# HYDRA_V4_NAV.net
KiCad netlist of a schematic drawn in Altium Designer
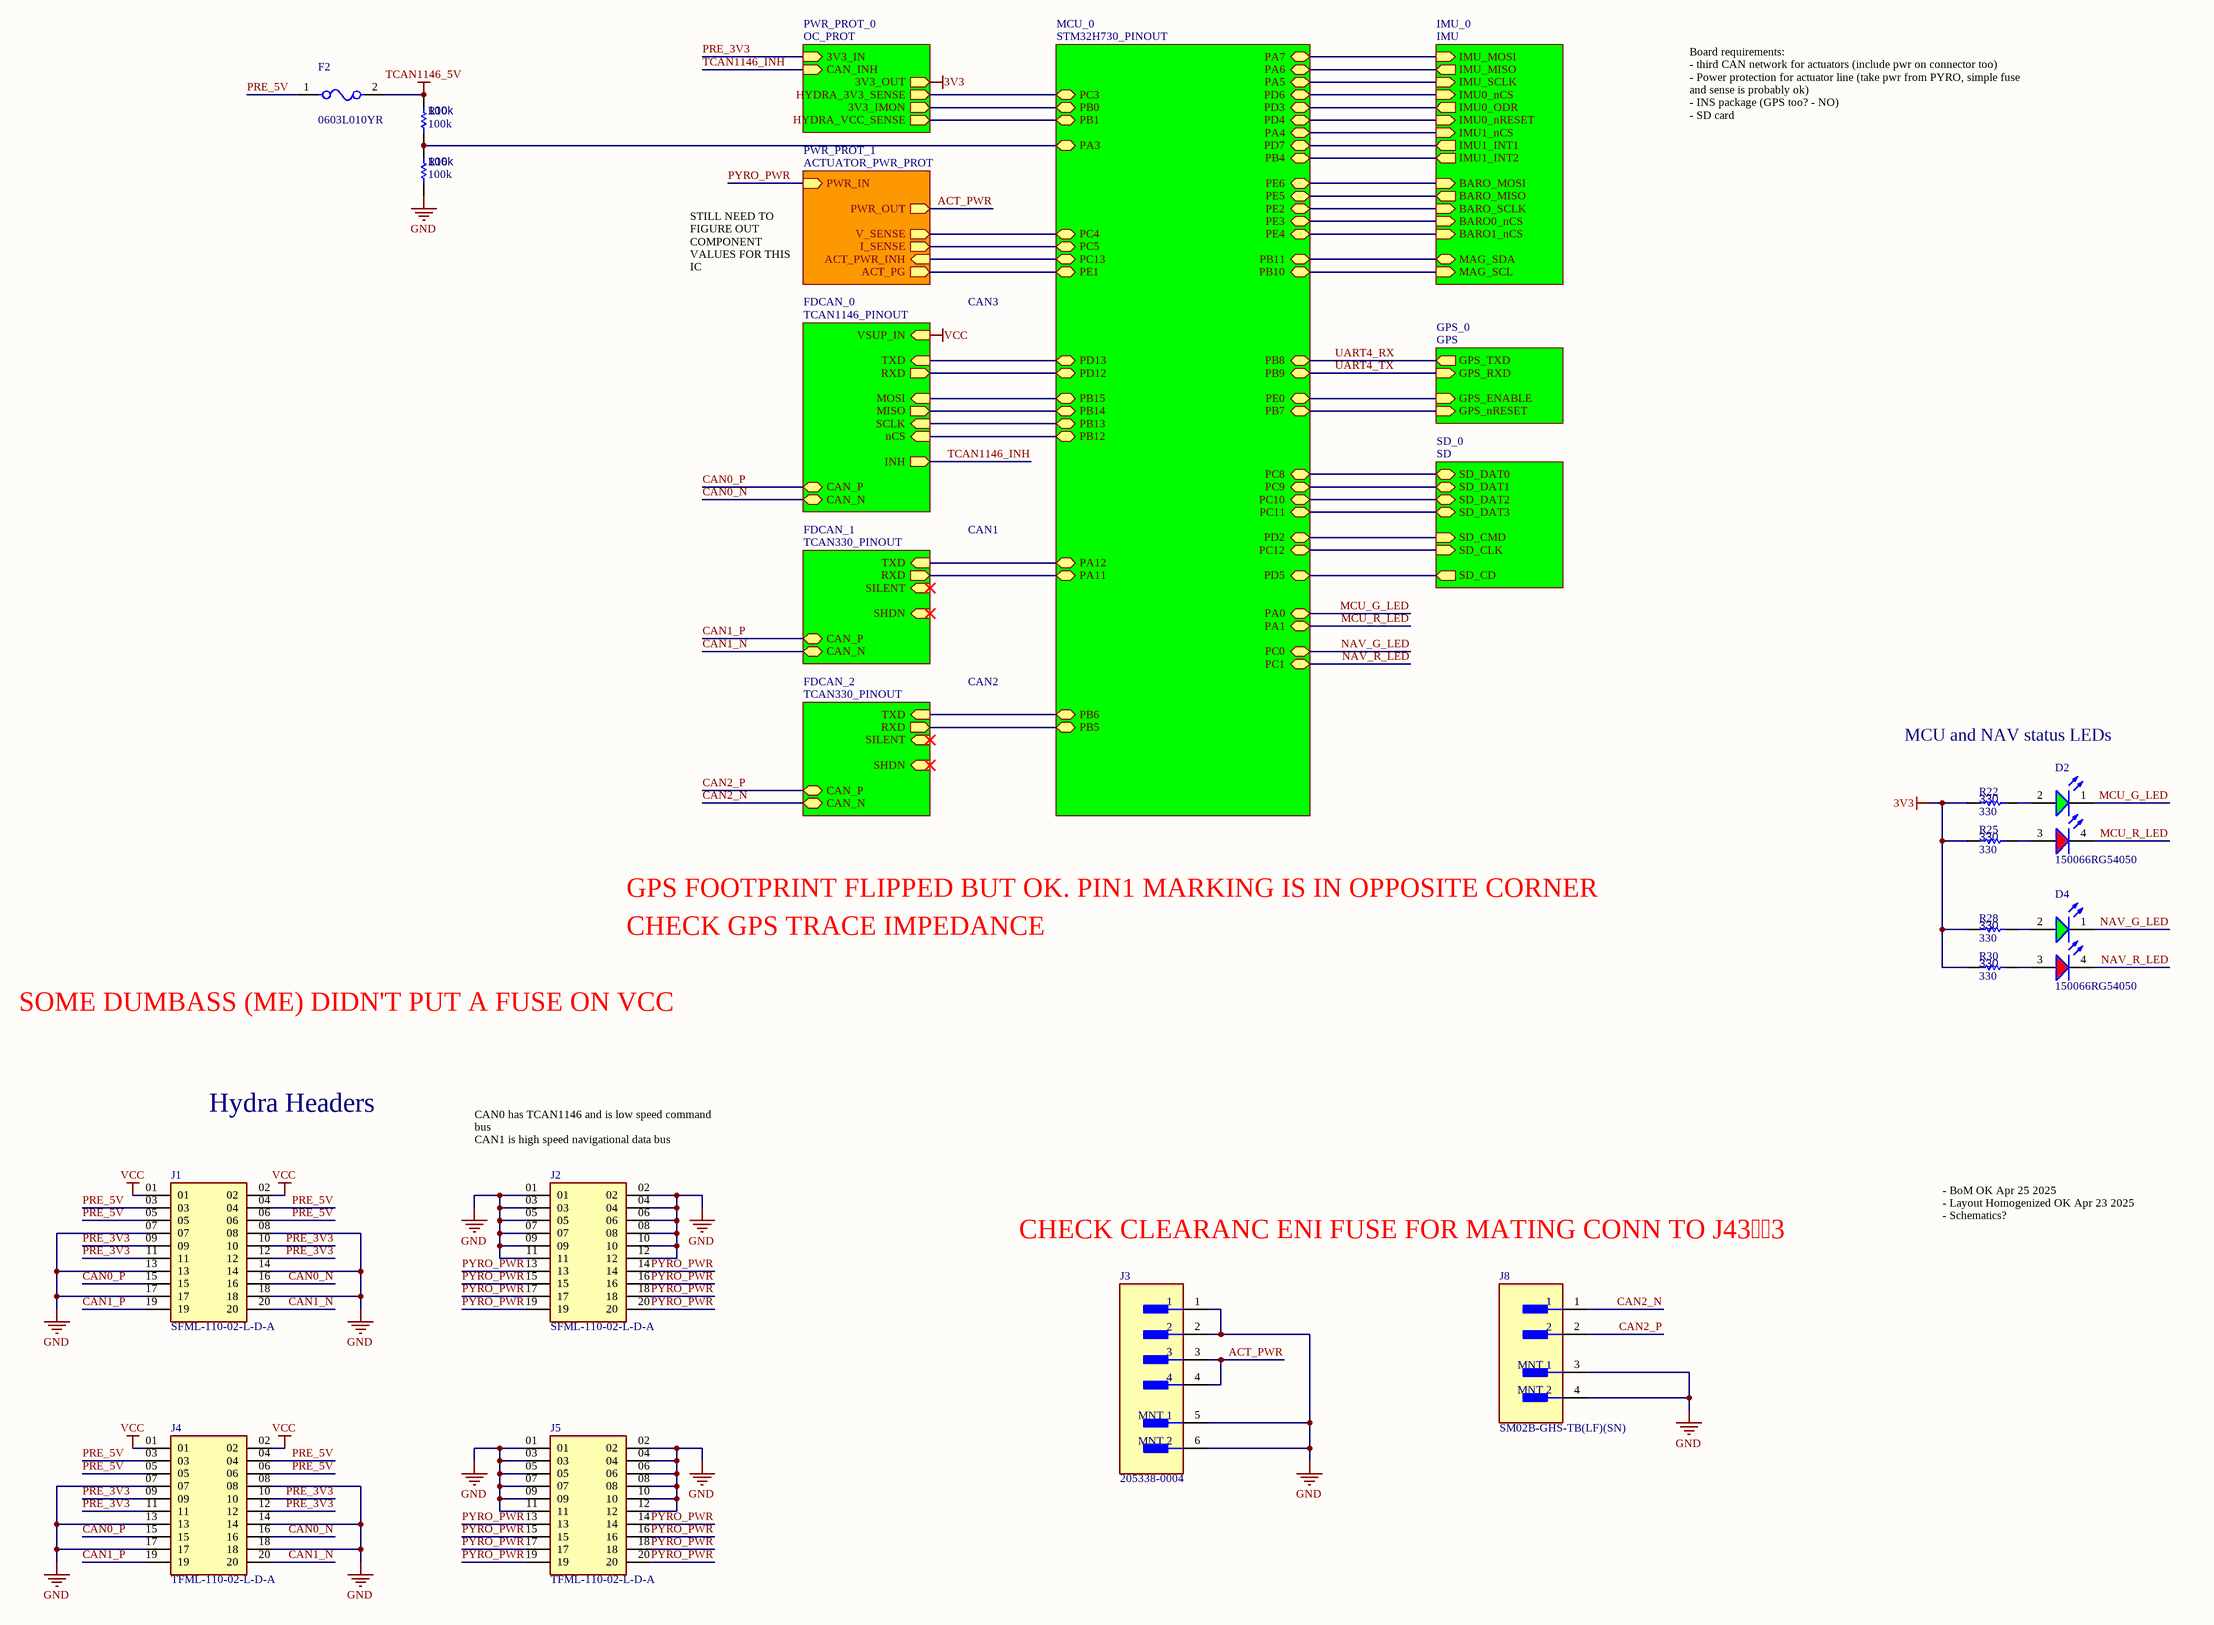
[diagram p0: HYDRA_V4_NAV.SchDoc]

(export (version "E")
  (design (tool "Eeschema 10.0.6"))
  (components
    (comp (ref "D2")
      (value "150066RG54050")
      (footprint "WL-SBCD_0606")
      (description "Led, Red/Grn, 180Mcd/230Mcd, 624Nm/525Nm Rohs Compliant: Yes")
      (fields (field (name "SOURCE") "rgled.SchLib"))
      (libsource (lib "Space Concordia") (part "CMP-004-00034-2"))
    )
    (comp (ref "D4")
      (value "150066RG54050")
      (footprint "WL-SBCD_0606")
      (description "Led, Red/Grn, 180Mcd/230Mcd, 624Nm/525Nm Rohs Compliant: Yes")
      (fields (field (name "SOURCE") "rgled.SchLib"))
      (libsource (lib "Space Concordia") (part "CMP-004-00034-2"))
    )
    (comp (ref "F2")
      (value "0603L010YR")
      (footprint "FP-0603L-MFG")
      (description "PTC RESET FUSE 15V 100MA 0603")
      (fields
        (field (name "OCTOPART") "https://octopart.com/0603l010yr-littelfuse-8316166")
        (field (name "MANUFACTURER") "Littelfuse Inc")
      )
      (libsource (lib "Altium Content Vault") (part "5bcf9b9f640e542cf0359d10258e979"))
    )
    (comp (ref "J1")
      (value "SFML-110-02-L-D-A")
      (footprint "SFML-110-02-L-D-A-Footprint-1")
      (libsource (lib "Space Concordia") (part "SFML-110-02-L-D-A"))
    )
    (comp (ref "J2")
      (value "SFML-110-02-L-D-A")
      (footprint "SFML-110-02-L-D-A-Footprint-1")
      (libsource (lib "Space Concordia") (part "SFML-110-02-L-D-A"))
    )
    (comp (ref "J3")
      (value "205338-0004")
      (footprint "FP-205338-0004-MFG")
      (description "PICO-LOCK 2.0 W/B HEADER ASSY ET")
      (libsource (lib "Altium Content Vault") (part "3b6f738a5616415d78381ad43816e4a"))
    )
    (comp (ref "J4")
      (value "TFML-110-02-L-D-A")
      (footprint "TFML-110-02-L-D-A-Footprint-1")
      (description "Board Connector, 20 Contact(s), 2 Row(s), Male, Straight, Surface Mount Terminal")
      (libsource (lib "Space Concordia") (part "TFML-110-02-L-D-A"))
    )
    (comp (ref "J5")
      (value "TFML-110-02-L-D-A")
      (footprint "TFML-110-02-L-D-A-Footprint-1")
      (description "Board Connector, 20 Contact(s), 2 Row(s), Male, Straight, Surface Mount Terminal")
      (libsource (lib "Space Concordia") (part "TFML-110-02-L-D-A"))
    )
    (comp (ref "J8")
      (value "SM02B-GHS-TB(LF)(SN)")
      (footprint "FP-SM02B-GHS-TB_LF_SN-MFG")
      (description "MCU 32-bit LPC1800 ARM Cortex M3 RISC 768KB Flash 3.3V 100-Pin TFBGA Tray")
      (libsource (lib "Space Concordia") (part "56ec3178a87b3978bdc1b3682cd516a"))
    )
    (comp (ref "R10")
      (value "100k")
      (footprint "R0603B")
      (description "Resistor")
      (fields (field (name "ALTIUM_VALUE") "100k"))
      (libsource (lib "Space Concordia") (part "Resistor"))
    )
    (comp (ref "R16")
      (value "100k")
      (footprint "R0603B")
      (description "Resistor")
      (fields (field (name "ALTIUM_VALUE") "100k"))
      (libsource (lib "Space Concordia") (part "Resistor"))
    )
    (comp (ref "R22")
      (value "330")
      (footprint "R0603B")
      (description "Resistor")
      (fields (field (name "ALTIUM_VALUE") "330"))
      (libsource (lib "Space Concordia") (part "Resistor"))
    )
    (comp (ref "R25")
      (value "330")
      (footprint "R0603B")
      (description "Resistor")
      (fields (field (name "ALTIUM_VALUE") "330"))
      (libsource (lib "Space Concordia") (part "Resistor"))
    )
    (comp (ref "R28")
      (value "330")
      (footprint "R0603B")
      (description "Resistor")
      (fields (field (name "ALTIUM_VALUE") "330"))
      (libsource (lib "Space Concordia") (part "Resistor"))
    )
    (comp (ref "R30")
      (value "330")
      (footprint "R0603B")
      (description "Resistor")
      (fields (field (name "ALTIUM_VALUE") "330"))
      (libsource (lib "Space Concordia") (part "Resistor"))
    )
  )
  (nets
    (net (code "3") (name "/ACT_PWR") (class "Default")
      (node (ref "J3") (pin "3") (pinfunction "3_3") (pintype "passive"))
      (node (ref "J3") (pin "4") (pinfunction "4_4") (pintype "passive"))
    )
    (net (code "10") (name "/CAN0_N") (class "Default")
      (node (ref "J1") (pin "16") (pinfunction "16_16") (pintype "passive"))
      (node (ref "J4") (pin "16") (pinfunction "16_16") (pintype "passive"))
    )
    (net (code "11") (name "/CAN0_P") (class "Default")
      (node (ref "J1") (pin "15") (pinfunction "15_15") (pintype "passive"))
      (node (ref "J4") (pin "15") (pinfunction "15_15") (pintype "passive"))
    )
    (net (code "12") (name "/CAN1_N") (class "Default")
      (node (ref "J1") (pin "20") (pinfunction "20_20") (pintype "passive"))
      (node (ref "J4") (pin "20") (pinfunction "20_20") (pintype "passive"))
    )
    (net (code "13") (name "/CAN1_P") (class "Default")
      (node (ref "J1") (pin "19") (pinfunction "19_19") (pintype "passive"))
      (node (ref "J4") (pin "19") (pinfunction "19_19") (pintype "passive"))
    )
    (net (code "14") (name "/CAN2_N") (class "Default")
      (node (ref "J8") (pin "1") (pinfunction "1_1") (pintype "passive"))
    )
    (net (code "15") (name "/CAN2_P") (class "Default")
      (node (ref "J8") (pin "2") (pinfunction "2_2") (pintype "passive"))
    )
    (net (code "32") (name "/MCU_G_LED") (class "Default")
      (node (ref "D2") (pin "1") (pinfunction "K_1") (pintype "passive"))
    )
    (net (code "33") (name "/MCU_R_LED") (class "Default")
      (node (ref "D2") (pin "4") (pinfunction "K_4") (pintype "passive"))
    )
    (net (code "36") (name "/NAV_G_LED") (class "Default")
      (node (ref "D4") (pin "1") (pinfunction "K_1") (pintype "passive"))
    )
    (net (code "37") (name "/NAV_R_LED") (class "Default")
      (node (ref "D4") (pin "4") (pinfunction "K_4") (pintype "passive"))
    )
    (net (code "38") (name "/PA3") (class "Default")
      (node (ref "R10") (pin "2") (pinfunction "2_2") (pintype "passive"))
      (node (ref "R16") (pin "1") (pinfunction "1_1") (pintype "passive"))
    )
    (net (code "50") (name "/PRE_3V3") (class "Default")
      (node (ref "J1") (pin "09") (pinfunction "09_09") (pintype "passive"))
      (node (ref "J1") (pin "10") (pinfunction "10_10") (pintype "passive"))
      (node (ref "J1") (pin "11") (pinfunction "11_11") (pintype "passive"))
      (node (ref "J1") (pin "12") (pinfunction "12_12") (pintype "passive"))
      (node (ref "J4") (pin "09") (pinfunction "09_09") (pintype "passive"))
      (node (ref "J4") (pin "10") (pinfunction "10_10") (pintype "passive"))
      (node (ref "J4") (pin "11") (pinfunction "11_11") (pintype "passive"))
      (node (ref "J4") (pin "12") (pinfunction "12_12") (pintype "passive"))
    )
    (net (code "51") (name "/PRE_5V") (class "Default")
      (node (ref "F2") (pin "1") (pinfunction "1_1") (pintype "passive"))
      (node (ref "J1") (pin "03") (pinfunction "03_03") (pintype "passive"))
      (node (ref "J1") (pin "04") (pinfunction "04_04") (pintype "passive"))
      (node (ref "J1") (pin "05") (pinfunction "05_05") (pintype "passive"))
      (node (ref "J1") (pin "06") (pinfunction "06_06") (pintype "passive"))
      (node (ref "J4") (pin "03") (pinfunction "03_03") (pintype "passive"))
      (node (ref "J4") (pin "04") (pinfunction "04_04") (pintype "passive"))
      (node (ref "J4") (pin "05") (pinfunction "05_05") (pintype "passive"))
      (node (ref "J4") (pin "06") (pinfunction "06_06") (pintype "passive"))
    )
    (net (code "52") (name "/PYRO_PWR") (class "Default")
      (node (ref "J2") (pin "13") (pinfunction "13_13") (pintype "passive"))
      (node (ref "J2") (pin "14") (pinfunction "14_14") (pintype "passive"))
      (node (ref "J2") (pin "15") (pinfunction "15_15") (pintype "passive"))
      (node (ref "J2") (pin "16") (pinfunction "16_16") (pintype "passive"))
      (node (ref "J2") (pin "17") (pinfunction "17_17") (pintype "passive"))
      (node (ref "J2") (pin "18") (pinfunction "18_18") (pintype "passive"))
      (node (ref "J2") (pin "19") (pinfunction "19_19") (pintype "passive"))
      (node (ref "J2") (pin "20") (pinfunction "20_20") (pintype "passive"))
      (node (ref "J5") (pin "13") (pinfunction "13_13") (pintype "passive"))
      (node (ref "J5") (pin "14") (pinfunction "14_14") (pintype "passive"))
      (node (ref "J5") (pin "15") (pinfunction "15_15") (pintype "passive"))
      (node (ref "J5") (pin "16") (pinfunction "16_16") (pintype "passive"))
      (node (ref "J5") (pin "17") (pinfunction "17_17") (pintype "passive"))
      (node (ref "J5") (pin "18") (pinfunction "18_18") (pintype "passive"))
      (node (ref "J5") (pin "19") (pinfunction "19_19") (pintype "passive"))
      (node (ref "J5") (pin "20") (pinfunction "20_20") (pintype "passive"))
    )
    (net (code "65") (name "3V3") (class "Default")
      (node (ref "R22") (pin "1") (pinfunction "1_1") (pintype "passive"))
      (node (ref "R25") (pin "1") (pinfunction "1_1") (pintype "passive"))
      (node (ref "R28") (pin "1") (pinfunction "1_1") (pintype "passive"))
      (node (ref "R30") (pin "1") (pinfunction "1_1") (pintype "passive"))
    )
    (net (code "66") (name "GND") (class "Default")
      (node (ref "J1") (pin "07") (pinfunction "07_07") (pintype "passive"))
      (node (ref "J1") (pin "08") (pinfunction "08_08") (pintype "passive"))
      (node (ref "J1") (pin "13") (pinfunction "13_13") (pintype "passive"))
      (node (ref "J1") (pin "14") (pinfunction "14_14") (pintype "passive"))
      (node (ref "J1") (pin "17") (pinfunction "17_17") (pintype "passive"))
      (node (ref "J1") (pin "18") (pinfunction "18_18") (pintype "passive"))
      (node (ref "J2") (pin "01") (pinfunction "01_01") (pintype "passive"))
      (node (ref "J2") (pin "02") (pinfunction "02_02") (pintype "passive"))
      (node (ref "J2") (pin "03") (pinfunction "03_03") (pintype "passive"))
      (node (ref "J2") (pin "04") (pinfunction "04_04") (pintype "passive"))
      (node (ref "J2") (pin "05") (pinfunction "05_05") (pintype "passive"))
      (node (ref "J2") (pin "06") (pinfunction "06_06") (pintype "passive"))
      (node (ref "J2") (pin "07") (pinfunction "07_07") (pintype "passive"))
      (node (ref "J2") (pin "08") (pinfunction "08_08") (pintype "passive"))
      (node (ref "J2") (pin "09") (pinfunction "09_09") (pintype "passive"))
      (node (ref "J2") (pin "10") (pinfunction "10_10") (pintype "passive"))
      (node (ref "J2") (pin "11") (pinfunction "11_11") (pintype "passive"))
      (node (ref "J2") (pin "12") (pinfunction "12_12") (pintype "passive"))
      (node (ref "J3") (pin "1") (pinfunction "1_1") (pintype "passive"))
      (node (ref "J3") (pin "2") (pinfunction "2_2") (pintype "passive"))
      (node (ref "J3") (pin "5") (pinfunction "MNT_1_5") (pintype "passive"))
      (node (ref "J3") (pin "6") (pinfunction "MNT_2_6") (pintype "passive"))
      (node (ref "J4") (pin "07") (pinfunction "07_07") (pintype "passive"))
      (node (ref "J4") (pin "08") (pinfunction "08_08") (pintype "passive"))
      (node (ref "J4") (pin "13") (pinfunction "13_13") (pintype "passive"))
      (node (ref "J4") (pin "14") (pinfunction "14_14") (pintype "passive"))
      (node (ref "J4") (pin "17") (pinfunction "17_17") (pintype "passive"))
      (node (ref "J4") (pin "18") (pinfunction "18_18") (pintype "passive"))
      (node (ref "J5") (pin "01") (pinfunction "01_01") (pintype "passive"))
      (node (ref "J5") (pin "02") (pinfunction "02_02") (pintype "passive"))
      (node (ref "J5") (pin "03") (pinfunction "03_03") (pintype "passive"))
      (node (ref "J5") (pin "04") (pinfunction "04_04") (pintype "passive"))
      (node (ref "J5") (pin "05") (pinfunction "05_05") (pintype "passive"))
      (node (ref "J5") (pin "06") (pinfunction "06_06") (pintype "passive"))
      (node (ref "J5") (pin "07") (pinfunction "07_07") (pintype "passive"))
      (node (ref "J5") (pin "08") (pinfunction "08_08") (pintype "passive"))
      (node (ref "J5") (pin "09") (pinfunction "09_09") (pintype "passive"))
      (node (ref "J5") (pin "10") (pinfunction "10_10") (pintype "passive"))
      (node (ref "J5") (pin "11") (pinfunction "11_11") (pintype "passive"))
      (node (ref "J5") (pin "12") (pinfunction "12_12") (pintype "passive"))
      (node (ref "J8") (pin "3") (pinfunction "MNT_1_3") (pintype "passive"))
      (node (ref "J8") (pin "4") (pinfunction "MNT_2_4") (pintype "passive"))
      (node (ref "R16") (pin "2") (pinfunction "2_2") (pintype "passive"))
    )
    (net (code "67") (name "Net-(D2-A-Pad2)") (class "Default")
      (node (ref "D2") (pin "2") (pinfunction "A_2") (pintype "passive"))
      (node (ref "R22") (pin "2") (pinfunction "2_2") (pintype "passive"))
    )
    (net (code "68") (name "Net-(D2-A-Pad3)") (class "Default")
      (node (ref "D2") (pin "3") (pinfunction "A_3") (pintype "passive"))
      (node (ref "R25") (pin "2") (pinfunction "2_2") (pintype "passive"))
    )
    (net (code "69") (name "Net-(D4-A-Pad2)") (class "Default")
      (node (ref "D4") (pin "2") (pinfunction "A_2") (pintype "passive"))
      (node (ref "R28") (pin "2") (pinfunction "2_2") (pintype "passive"))
    )
    (net (code "70") (name "Net-(D4-A-Pad3)") (class "Default")
      (node (ref "D4") (pin "3") (pinfunction "A_3") (pintype "passive"))
      (node (ref "R30") (pin "2") (pinfunction "2_2") (pintype "passive"))
    )
    (net (code "71") (name "TCAN1146_5V") (class "Default")
      (node (ref "F2") (pin "2") (pinfunction "2_2") (pintype "passive"))
      (node (ref "R10") (pin "1") (pinfunction "1_1") (pintype "passive"))
    )
    (net (code "72") (name "VCC") (class "Default")
      (node (ref "J1") (pin "01") (pinfunction "01_01") (pintype "passive"))
      (node (ref "J1") (pin "02") (pinfunction "02_02") (pintype "passive"))
      (node (ref "J4") (pin "01") (pinfunction "01_01") (pintype "passive"))
      (node (ref "J4") (pin "02") (pinfunction "02_02") (pintype "passive"))
    )
  )
)
